# TTGO_shield_revF.net
KiCad netlist of a schematic drawn in EAGLE
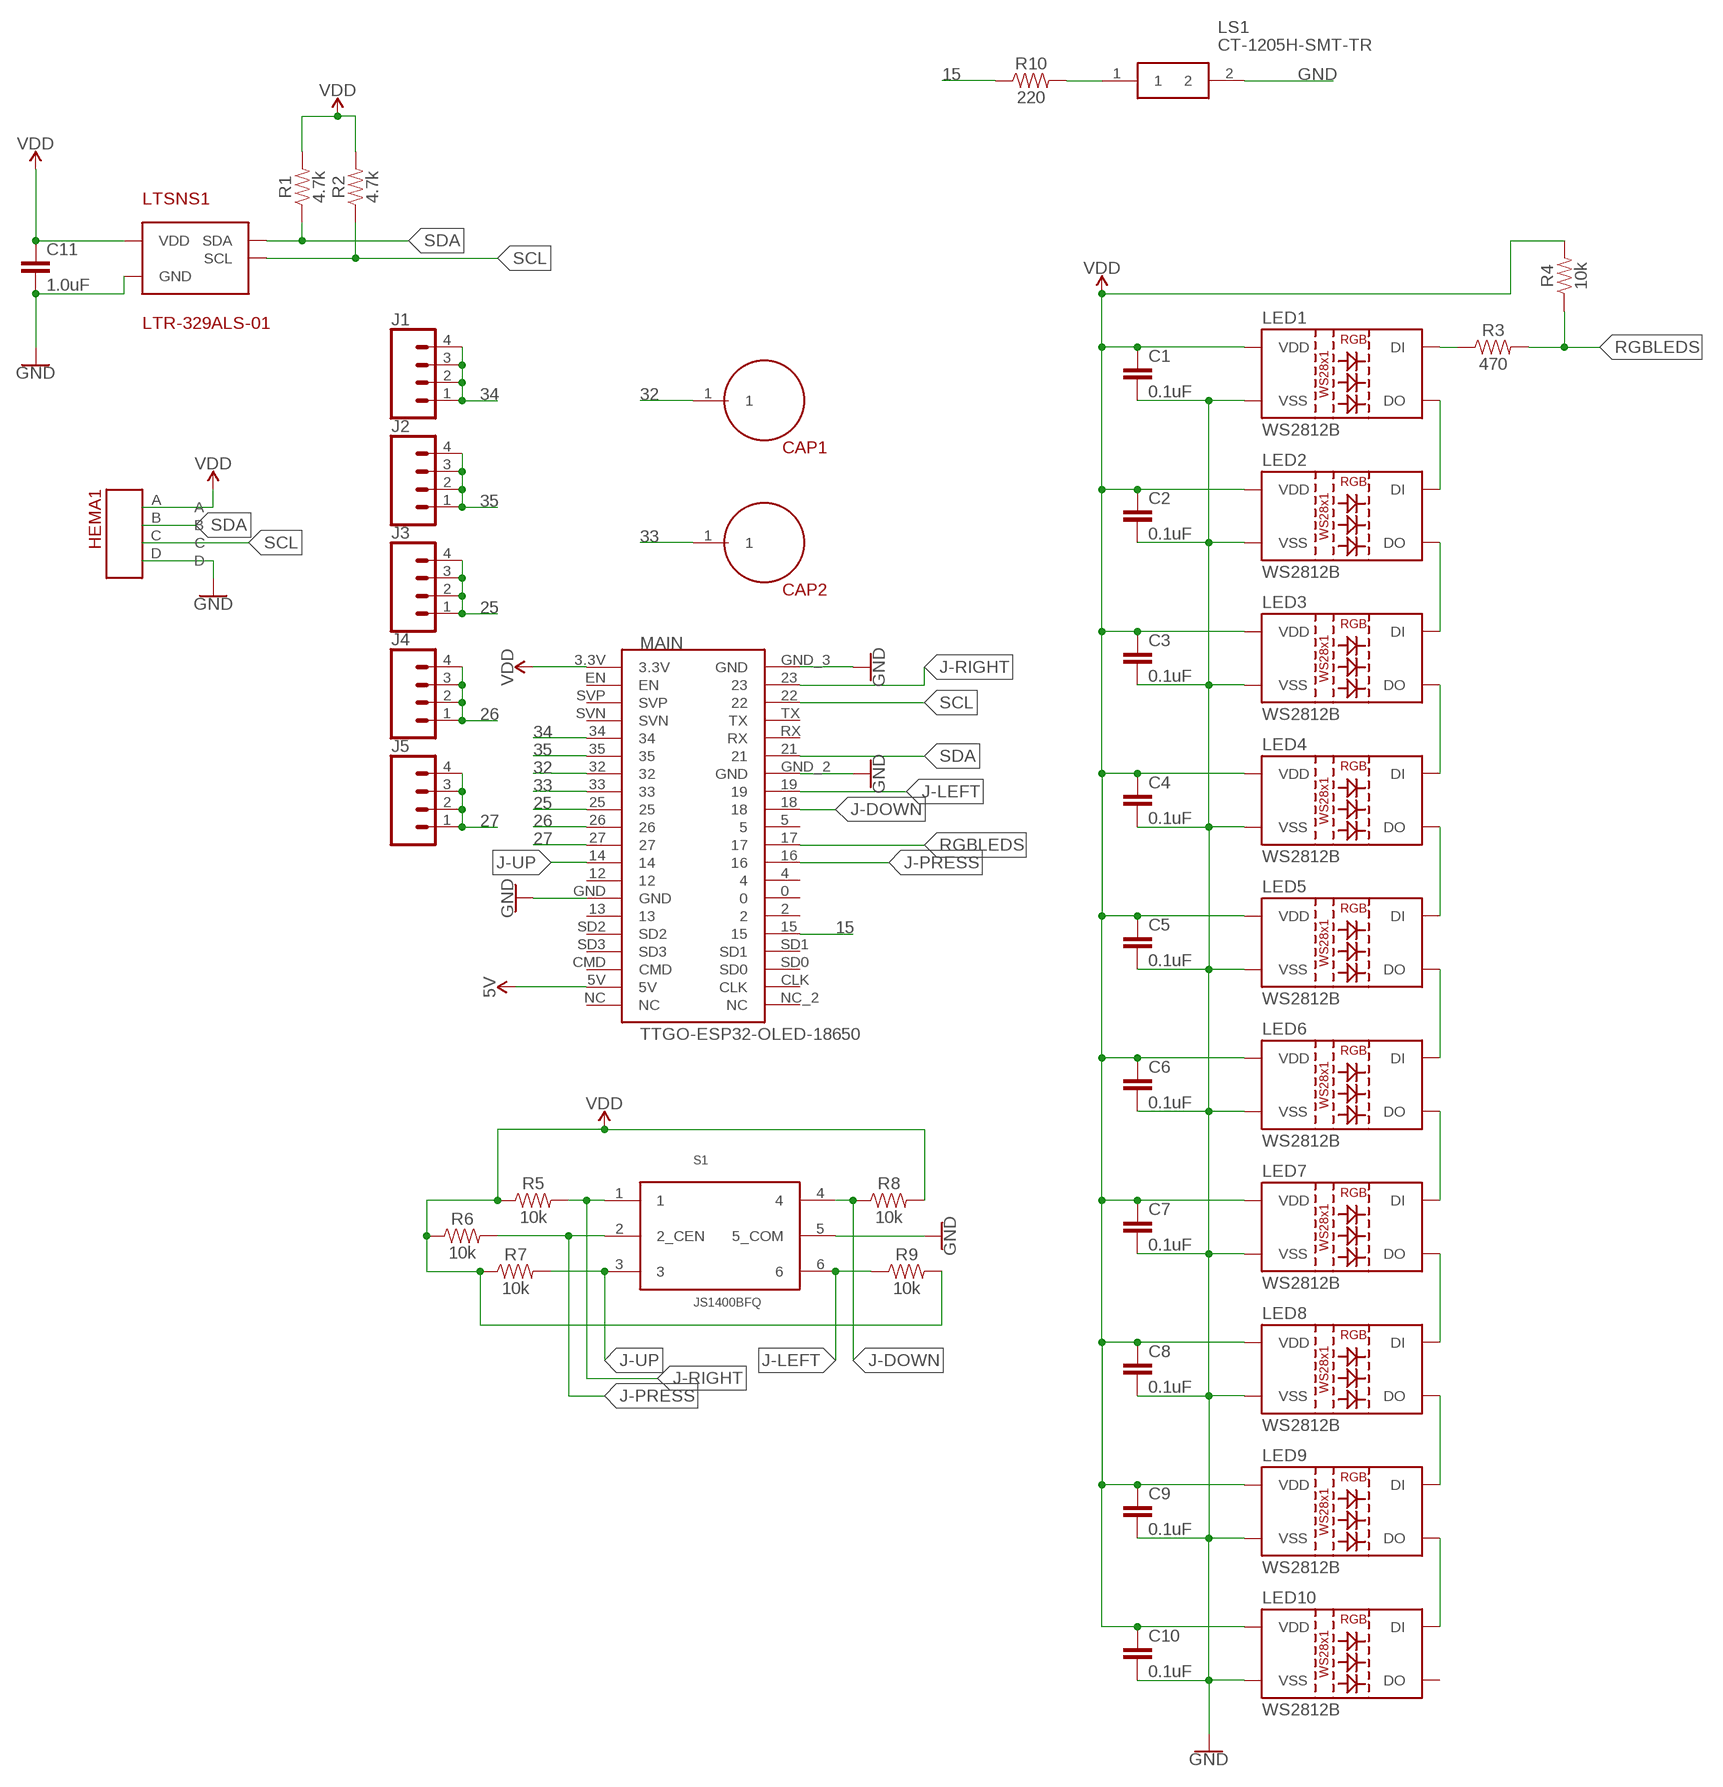
[diagram p0: schematic, sheet 1]

(export (version "E")
  (design (tool "Eeschema 10.0.6"))
  (components
    (comp (ref "C1")
      (value "0.1uF")
      (footprint "eagle-import:0603")
      (libsource (lib "eagle-import") (part "0.1UF-0603-25V-5%"))
    )
    (comp (ref "C2")
      (value "0.1uF")
      (footprint "eagle-import:0603")
      (libsource (lib "eagle-import") (part "0.1UF-0603-25V-5%"))
    )
    (comp (ref "C3")
      (value "0.1uF")
      (footprint "eagle-import:0603")
      (libsource (lib "eagle-import") (part "0.1UF-0603-25V-5%"))
    )
    (comp (ref "C4")
      (value "0.1uF")
      (footprint "eagle-import:0603")
      (libsource (lib "eagle-import") (part "0.1UF-0603-25V-5%"))
    )
    (comp (ref "C5")
      (value "0.1uF")
      (footprint "eagle-import:0603")
      (libsource (lib "eagle-import") (part "0.1UF-0603-25V-5%"))
    )
    (comp (ref "C6")
      (value "0.1uF")
      (footprint "eagle-import:0603")
      (libsource (lib "eagle-import") (part "0.1UF-0603-25V-5%"))
    )
    (comp (ref "C7")
      (value "0.1uF")
      (footprint "eagle-import:0603")
      (libsource (lib "eagle-import") (part "0.1UF-0603-25V-5%"))
    )
    (comp (ref "C8")
      (value "0.1uF")
      (footprint "eagle-import:0603")
      (libsource (lib "eagle-import") (part "0.1UF-0603-25V-5%"))
    )
    (comp (ref "C9")
      (value "0.1uF")
      (footprint "eagle-import:0603")
      (libsource (lib "eagle-import") (part "0.1UF-0603-25V-5%"))
    )
    (comp (ref "C10")
      (value "0.1uF")
      (footprint "eagle-import:0603")
      (libsource (lib "eagle-import") (part "0.1UF-0603-25V-5%"))
    )
    (comp (ref "C11")
      (value "1.0uF")
      (footprint "eagle-import:0805")
      (libsource (lib "eagle-import") (part "1.0UF-0805-25V-10%"))
    )
    (comp (ref "CAP1")
      (value "CAPSENSE_BUTTON")
      (footprint "eagle-import:CAPSENSE_BUTTON")
      (libsource (lib "eagle-import") (part "CAPSENSE_BUTTON"))
    )
    (comp (ref "CAP2")
      (value "CAPSENSE_BUTTON")
      (footprint "eagle-import:CAPSENSE_BUTTON")
      (libsource (lib "eagle-import") (part "CAPSENSE_BUTTON"))
    )
    (comp (ref "HEMA1")
      (value "10120045-400LF")
      (footprint "eagle-import:10120045-400LF")
      (libsource (lib "eagle-import") (part "10120045-400LF"))
    )
    (comp (ref "J1")
      (value "CONN_04LONGPADS")
      (footprint "eagle-import:1X04_LONGPADS")
      (libsource (lib "eagle-import") (part "CONN_04LONGPADS"))
    )
    (comp (ref "J2")
      (value "CONN_04LONGPADS")
      (footprint "eagle-import:1X04_LONGPADS")
      (libsource (lib "eagle-import") (part "CONN_04LONGPADS"))
    )
    (comp (ref "J3")
      (value "CONN_04LONGPADS")
      (footprint "eagle-import:1X04_LONGPADS")
      (libsource (lib "eagle-import") (part "CONN_04LONGPADS"))
    )
    (comp (ref "J4")
      (value "CONN_04LONGPADS")
      (footprint "eagle-import:1X04_LONGPADS")
      (libsource (lib "eagle-import") (part "CONN_04LONGPADS"))
    )
    (comp (ref "J5")
      (value "CONN_04LONGPADS")
      (footprint "eagle-import:1X04_LONGPADS")
      (libsource (lib "eagle-import") (part "CONN_04LONGPADS"))
    )
    (comp (ref "LED1")
      (value "WS2812B")
      (footprint "eagle-import:WS2812B")
      (libsource (lib "eagle-import") (part "WS2812B"))
    )
    (comp (ref "LED2")
      (value "WS2812B")
      (footprint "eagle-import:WS2812B")
      (libsource (lib "eagle-import") (part "WS2812B"))
    )
    (comp (ref "LED3")
      (value "WS2812B")
      (footprint "eagle-import:WS2812B")
      (libsource (lib "eagle-import") (part "WS2812B"))
    )
    (comp (ref "LED4")
      (value "WS2812B")
      (footprint "eagle-import:WS2812B")
      (libsource (lib "eagle-import") (part "WS2812B"))
    )
    (comp (ref "LED5")
      (value "WS2812B")
      (footprint "eagle-import:WS2812B")
      (libsource (lib "eagle-import") (part "WS2812B"))
    )
    (comp (ref "LED6")
      (value "WS2812B")
      (footprint "eagle-import:WS2812B")
      (libsource (lib "eagle-import") (part "WS2812B"))
    )
    (comp (ref "LED7")
      (value "WS2812B")
      (footprint "eagle-import:WS2812B")
      (libsource (lib "eagle-import") (part "WS2812B"))
    )
    (comp (ref "LED8")
      (value "WS2812B")
      (footprint "eagle-import:WS2812B")
      (libsource (lib "eagle-import") (part "WS2812B"))
    )
    (comp (ref "LED9")
      (value "WS2812B")
      (footprint "eagle-import:WS2812B")
      (libsource (lib "eagle-import") (part "WS2812B"))
    )
    (comp (ref "LED10")
      (value "WS2812B")
      (footprint "eagle-import:WS2812B")
      (libsource (lib "eagle-import") (part "WS2812B"))
    )
    (comp (ref "LS1")
      (value "CT-1205H-SMT-TR")
      (footprint "eagle-import:CT1205HSMTTR")
      (libsource (lib "eagle-import") (part "CT-1205H-SMT-TR"))
    )
    (comp (ref "LTSNS1")
      (value "LTR-329ALS-01")
      (footprint "eagle-import:CHIPLED-4")
      (libsource (lib "eagle-import") (part "LTR-329ALS-01"))
    )
    (comp (ref "MAIN")
      (value "TTGO-ESP32-OLED-18650")
      (footprint "eagle-import:TTGO-ESP32-OLED-18650")
      (libsource (lib "eagle-import") (part "TTGO-ESP32-OLED-18650"))
    )
    (comp (ref "R1")
      (value "4.7k")
      (footprint "eagle-import:0603")
      (libsource (lib "eagle-import") (part "4.7KOHM-0603-1/10W-1%"))
    )
    (comp (ref "R2")
      (value "4.7k")
      (footprint "eagle-import:0603")
      (libsource (lib "eagle-import") (part "4.7KOHM-0603-1/10W-1%"))
    )
    (comp (ref "R3")
      (value "470")
      (footprint "eagle-import:0603")
      (libsource (lib "eagle-import") (part "470OHM-0603-1/10W-1%"))
    )
    (comp (ref "R4")
      (value "10k")
      (footprint "eagle-import:0603")
      (libsource (lib "eagle-import") (part "10KOHM-0603-1/10W-1%"))
    )
    (comp (ref "R5")
      (value "10k")
      (footprint "eagle-import:0603")
      (libsource (lib "eagle-import") (part "10KOHM-0603-1/10W-1%"))
    )
    (comp (ref "R6")
      (value "10k")
      (footprint "eagle-import:0603")
      (libsource (lib "eagle-import") (part "10KOHM-0603-1/10W-1%"))
    )
    (comp (ref "R7")
      (value "10k")
      (footprint "eagle-import:0603")
      (libsource (lib "eagle-import") (part "10KOHM-0603-1/10W-1%"))
    )
    (comp (ref "R8")
      (value "10k")
      (footprint "eagle-import:0603")
      (libsource (lib "eagle-import") (part "10KOHM-0603-1/10W-1%"))
    )
    (comp (ref "R9")
      (value "10k")
      (footprint "eagle-import:0603")
      (libsource (lib "eagle-import") (part "10KOHM-0603-1/10W-1%"))
    )
    (comp (ref "R10")
      (value "220")
      (footprint "eagle-import:0603")
      (libsource (lib "eagle-import") (part "470OHM-0603-1/10W-1%"))
    )
    (comp (ref "S1")
      (value "JS1400BFQ")
      (footprint "eagle-import:JS1400BFQ")
      (libsource (lib "eagle-import") (part "JS1400BFQ"))
    )
  )
  (nets
    (net (code "1") (name "/15") (class "Default")
      (node (ref "MAIN") (pin "15") (pinfunction "15_15") (pintype "bidirectional"))
      (node (ref "R10") (pin "1") (pinfunction "1_1") (pintype "passive"))
    )
    (net (code "2") (name "/25") (class "Default")
      (node (ref "J3") (pin "1") (pinfunction "1_1") (pintype "passive"))
      (node (ref "J3") (pin "2") (pinfunction "2_2") (pintype "passive"))
      (node (ref "J3") (pin "3") (pinfunction "3_3") (pintype "passive"))
      (node (ref "J3") (pin "4") (pinfunction "4_4") (pintype "passive"))
      (node (ref "MAIN") (pin "25") (pinfunction "25_25") (pintype "bidirectional"))
    )
    (net (code "3") (name "/26") (class "Default")
      (node (ref "J4") (pin "1") (pinfunction "1_1") (pintype "passive"))
      (node (ref "J4") (pin "2") (pinfunction "2_2") (pintype "passive"))
      (node (ref "J4") (pin "3") (pinfunction "3_3") (pintype "passive"))
      (node (ref "J4") (pin "4") (pinfunction "4_4") (pintype "passive"))
      (node (ref "MAIN") (pin "26") (pinfunction "26_26") (pintype "bidirectional"))
    )
    (net (code "4") (name "/27") (class "Default")
      (node (ref "J5") (pin "1") (pinfunction "1_1") (pintype "passive"))
      (node (ref "J5") (pin "2") (pinfunction "2_2") (pintype "passive"))
      (node (ref "J5") (pin "3") (pinfunction "3_3") (pintype "passive"))
      (node (ref "J5") (pin "4") (pinfunction "4_4") (pintype "passive"))
      (node (ref "MAIN") (pin "27") (pinfunction "27_27") (pintype "bidirectional"))
    )
    (net (code "5") (name "/32") (class "Default")
      (node (ref "CAP1") (pin "1") (pinfunction "1_1") (pintype "bidirectional"))
      (node (ref "MAIN") (pin "32") (pinfunction "32_32") (pintype "bidirectional"))
    )
    (net (code "6") (name "/33") (class "Default")
      (node (ref "CAP2") (pin "1") (pinfunction "1_1") (pintype "bidirectional"))
      (node (ref "MAIN") (pin "33") (pinfunction "33_33") (pintype "bidirectional"))
    )
    (net (code "7") (name "/34") (class "Default")
      (node (ref "J1") (pin "1") (pinfunction "1_1") (pintype "passive"))
      (node (ref "J1") (pin "2") (pinfunction "2_2") (pintype "passive"))
      (node (ref "J1") (pin "3") (pinfunction "3_3") (pintype "passive"))
      (node (ref "J1") (pin "4") (pinfunction "4_4") (pintype "passive"))
      (node (ref "MAIN") (pin "34") (pinfunction "34_34") (pintype "bidirectional"))
    )
    (net (code "8") (name "/35") (class "Default")
      (node (ref "J2") (pin "1") (pinfunction "1_1") (pintype "passive"))
      (node (ref "J2") (pin "2") (pinfunction "2_2") (pintype "passive"))
      (node (ref "J2") (pin "3") (pinfunction "3_3") (pintype "passive"))
      (node (ref "J2") (pin "4") (pinfunction "4_4") (pintype "passive"))
      (node (ref "MAIN") (pin "35") (pinfunction "35_35") (pintype "bidirectional"))
    )
    (net (code "9") (name "5V") (class "Default")
      (node (ref "MAIN") (pin "5V") (pinfunction "5V_5V") (pintype "bidirectional"))
    )
    (net (code "10") (name "GND") (class "Default")
      (node (ref "C1") (pin "2") (pinfunction "2_2") (pintype "passive"))
      (node (ref "C10") (pin "2") (pinfunction "2_2") (pintype "passive"))
      (node (ref "C11") (pin "2") (pinfunction "2_2") (pintype "passive"))
      (node (ref "C2") (pin "2") (pinfunction "2_2") (pintype "passive"))
      (node (ref "C3") (pin "2") (pinfunction "2_2") (pintype "passive"))
      (node (ref "C4") (pin "2") (pinfunction "2_2") (pintype "passive"))
      (node (ref "C5") (pin "2") (pinfunction "2_2") (pintype "passive"))
      (node (ref "C6") (pin "2") (pinfunction "2_2") (pintype "passive"))
      (node (ref "C7") (pin "2") (pinfunction "2_2") (pintype "passive"))
      (node (ref "C8") (pin "2") (pinfunction "2_2") (pintype "passive"))
      (node (ref "C9") (pin "2") (pinfunction "2_2") (pintype "passive"))
      (node (ref "HEMA1") (pin "D") (pinfunction "D_D") (pintype "bidirectional"))
      (node (ref "LED1") (pin "3") (pinfunction "VSS_3") (pintype "bidirectional"))
      (node (ref "LED10") (pin "3") (pinfunction "VSS_3") (pintype "bidirectional"))
      (node (ref "LED2") (pin "3") (pinfunction "VSS_3") (pintype "bidirectional"))
      (node (ref "LED3") (pin "3") (pinfunction "VSS_3") (pintype "bidirectional"))
      (node (ref "LED4") (pin "3") (pinfunction "VSS_3") (pintype "bidirectional"))
      (node (ref "LED5") (pin "3") (pinfunction "VSS_3") (pintype "bidirectional"))
      (node (ref "LED6") (pin "3") (pinfunction "VSS_3") (pintype "bidirectional"))
      (node (ref "LED7") (pin "3") (pinfunction "VSS_3") (pintype "bidirectional"))
      (node (ref "LED8") (pin "3") (pinfunction "VSS_3") (pintype "bidirectional"))
      (node (ref "LED9") (pin "3") (pinfunction "VSS_3") (pintype "bidirectional"))
      (node (ref "LS1") (pin "2") (pinfunction "2_2") (pintype "bidirectional"))
      (node (ref "LTSNS1") (pin "2") (pinfunction "GND_2") (pintype "bidirectional"))
      (node (ref "MAIN") (pin "GND") (pinfunction "GND_GND") (pintype "bidirectional"))
      (node (ref "MAIN") (pin "GND_2") (pinfunction "GND_GND_2") (pintype "bidirectional"))
      (node (ref "MAIN") (pin "GND_3") (pinfunction "GND_GND_3") (pintype "bidirectional"))
      (node (ref "S1") (pin "5") (pinfunction "5_COM_5") (pintype "bidirectional"))
    )
    (net (code "11") (name "J-DOWN") (class "Default")
      (node (ref "MAIN") (pin "18") (pinfunction "18_18") (pintype "bidirectional"))
      (node (ref "R8") (pin "1") (pinfunction "1_1") (pintype "passive"))
      (node (ref "S1") (pin "4") (pinfunction "4_4") (pintype "bidirectional"))
    )
    (net (code "12") (name "J-LEFT") (class "Default")
      (node (ref "MAIN") (pin "19") (pinfunction "19_19") (pintype "bidirectional"))
      (node (ref "R9") (pin "1") (pinfunction "1_1") (pintype "passive"))
      (node (ref "S1") (pin "6") (pinfunction "6_6") (pintype "bidirectional"))
    )
    (net (code "13") (name "J-PRESS") (class "Default")
      (node (ref "MAIN") (pin "16") (pinfunction "16_16") (pintype "bidirectional"))
      (node (ref "R6") (pin "2") (pinfunction "2_2") (pintype "passive"))
      (node (ref "S1") (pin "2") (pinfunction "2_CEN_2") (pintype "bidirectional"))
    )
    (net (code "14") (name "J-RIGHT") (class "Default")
      (node (ref "MAIN") (pin "23") (pinfunction "23_23") (pintype "bidirectional"))
      (node (ref "R5") (pin "2") (pinfunction "2_2") (pintype "passive"))
      (node (ref "S1") (pin "1") (pinfunction "1_1") (pintype "bidirectional"))
    )
    (net (code "15") (name "J-UP") (class "Default")
      (node (ref "MAIN") (pin "14") (pinfunction "14_14") (pintype "bidirectional"))
      (node (ref "R7") (pin "2") (pinfunction "2_2") (pintype "passive"))
      (node (ref "S1") (pin "3") (pinfunction "3_3") (pintype "bidirectional"))
    )
    (net (code "16") (name "Net-(LED1-DI)") (class "Default")
      (node (ref "LED1") (pin "4") (pinfunction "DI_4") (pintype "bidirectional"))
      (node (ref "R3") (pin "1") (pinfunction "1_1") (pintype "passive"))
    )
    (net (code "17") (name "Net-(LED1-DO)") (class "Default")
      (node (ref "LED1") (pin "2") (pinfunction "DO_2") (pintype "bidirectional"))
      (node (ref "LED2") (pin "4") (pinfunction "DI_4") (pintype "bidirectional"))
    )
    (net (code "18") (name "Net-(LED2-DO)") (class "Default")
      (node (ref "LED2") (pin "2") (pinfunction "DO_2") (pintype "bidirectional"))
      (node (ref "LED3") (pin "4") (pinfunction "DI_4") (pintype "bidirectional"))
    )
    (net (code "19") (name "Net-(LED3-DO)") (class "Default")
      (node (ref "LED3") (pin "2") (pinfunction "DO_2") (pintype "bidirectional"))
      (node (ref "LED4") (pin "4") (pinfunction "DI_4") (pintype "bidirectional"))
    )
    (net (code "20") (name "Net-(LED4-DO)") (class "Default")
      (node (ref "LED4") (pin "2") (pinfunction "DO_2") (pintype "bidirectional"))
      (node (ref "LED5") (pin "4") (pinfunction "DI_4") (pintype "bidirectional"))
    )
    (net (code "21") (name "Net-(LED5-DO)") (class "Default")
      (node (ref "LED5") (pin "2") (pinfunction "DO_2") (pintype "bidirectional"))
      (node (ref "LED6") (pin "4") (pinfunction "DI_4") (pintype "bidirectional"))
    )
    (net (code "22") (name "Net-(LED6-DO)") (class "Default")
      (node (ref "LED6") (pin "2") (pinfunction "DO_2") (pintype "bidirectional"))
      (node (ref "LED7") (pin "4") (pinfunction "DI_4") (pintype "bidirectional"))
    )
    (net (code "23") (name "Net-(LED7-DO)") (class "Default")
      (node (ref "LED7") (pin "2") (pinfunction "DO_2") (pintype "bidirectional"))
      (node (ref "LED8") (pin "4") (pinfunction "DI_4") (pintype "bidirectional"))
    )
    (net (code "24") (name "Net-(LED8-DO)") (class "Default")
      (node (ref "LED8") (pin "2") (pinfunction "DO_2") (pintype "bidirectional"))
      (node (ref "LED9") (pin "4") (pinfunction "DI_4") (pintype "bidirectional"))
    )
    (net (code "25") (name "Net-(LED10-DI)") (class "Default")
      (node (ref "LED10") (pin "4") (pinfunction "DI_4") (pintype "bidirectional"))
      (node (ref "LED9") (pin "2") (pinfunction "DO_2") (pintype "bidirectional"))
    )
    (net (code "26") (name "Net-(LS1-Pad1)") (class "Default")
      (node (ref "LS1") (pin "1") (pinfunction "1_1") (pintype "bidirectional"))
      (node (ref "R10") (pin "2") (pinfunction "2_2") (pintype "passive"))
    )
    (net (code "27") (name "RGBLEDS") (class "Default")
      (node (ref "MAIN") (pin "17") (pinfunction "17_17") (pintype "bidirectional"))
      (node (ref "R3") (pin "2") (pinfunction "2_2") (pintype "passive"))
      (node (ref "R4") (pin "1") (pinfunction "1_1") (pintype "passive"))
    )
    (net (code "28") (name "SCL") (class "Default")
      (node (ref "HEMA1") (pin "C") (pinfunction "C_C") (pintype "bidirectional"))
      (node (ref "LTSNS1") (pin "4") (pinfunction "SCL_4") (pintype "bidirectional"))
      (node (ref "MAIN") (pin "22") (pinfunction "22_22") (pintype "bidirectional"))
      (node (ref "R2") (pin "1") (pinfunction "1_1") (pintype "passive"))
    )
    (net (code "29") (name "SDA") (class "Default")
      (node (ref "HEMA1") (pin "B") (pinfunction "B_B") (pintype "bidirectional"))
      (node (ref "LTSNS1") (pin "3") (pinfunction "SDA_3") (pintype "bidirectional"))
      (node (ref "MAIN") (pin "21") (pinfunction "21_21") (pintype "bidirectional"))
      (node (ref "R1") (pin "1") (pinfunction "1_1") (pintype "passive"))
    )
    (net (code "30") (name "VDD") (class "Default")
      (node (ref "C1") (pin "1") (pinfunction "1_1") (pintype "passive"))
      (node (ref "C10") (pin "1") (pinfunction "1_1") (pintype "passive"))
      (node (ref "C11") (pin "1") (pinfunction "1_1") (pintype "passive"))
      (node (ref "C2") (pin "1") (pinfunction "1_1") (pintype "passive"))
      (node (ref "C3") (pin "1") (pinfunction "1_1") (pintype "passive"))
      (node (ref "C4") (pin "1") (pinfunction "1_1") (pintype "passive"))
      (node (ref "C5") (pin "1") (pinfunction "1_1") (pintype "passive"))
      (node (ref "C6") (pin "1") (pinfunction "1_1") (pintype "passive"))
      (node (ref "C7") (pin "1") (pinfunction "1_1") (pintype "passive"))
      (node (ref "C8") (pin "1") (pinfunction "1_1") (pintype "passive"))
      (node (ref "C9") (pin "1") (pinfunction "1_1") (pintype "passive"))
      (node (ref "HEMA1") (pin "A") (pinfunction "A_A") (pintype "bidirectional"))
      (node (ref "LED1") (pin "1") (pinfunction "VDD_1") (pintype "bidirectional"))
      (node (ref "LED10") (pin "1") (pinfunction "VDD_1") (pintype "bidirectional"))
      (node (ref "LED2") (pin "1") (pinfunction "VDD_1") (pintype "bidirectional"))
      (node (ref "LED3") (pin "1") (pinfunction "VDD_1") (pintype "bidirectional"))
      (node (ref "LED4") (pin "1") (pinfunction "VDD_1") (pintype "bidirectional"))
      (node (ref "LED5") (pin "1") (pinfunction "VDD_1") (pintype "bidirectional"))
      (node (ref "LED6") (pin "1") (pinfunction "VDD_1") (pintype "bidirectional"))
      (node (ref "LED7") (pin "1") (pinfunction "VDD_1") (pintype "bidirectional"))
      (node (ref "LED8") (pin "1") (pinfunction "VDD_1") (pintype "bidirectional"))
      (node (ref "LED9") (pin "1") (pinfunction "VDD_1") (pintype "bidirectional"))
      (node (ref "LTSNS1") (pin "1") (pinfunction "VDD_1") (pintype "bidirectional"))
      (node (ref "MAIN") (pin "3.3V") (pinfunction "3.3V_3.3V") (pintype "bidirectional"))
      (node (ref "R1") (pin "2") (pinfunction "2_2") (pintype "passive"))
      (node (ref "R2") (pin "2") (pinfunction "2_2") (pintype "passive"))
      (node (ref "R4") (pin "2") (pinfunction "2_2") (pintype "passive"))
      (node (ref "R5") (pin "1") (pinfunction "1_1") (pintype "passive"))
      (node (ref "R6") (pin "1") (pinfunction "1_1") (pintype "passive"))
      (node (ref "R7") (pin "1") (pinfunction "1_1") (pintype "passive"))
      (node (ref "R8") (pin "2") (pinfunction "2_2") (pintype "passive"))
      (node (ref "R9") (pin "2") (pinfunction "2_2") (pintype "passive"))
    )
    (net (code "31") (name "unconnected-(LED10-DO-Pad2)") (class "Default")
      (node (ref "LED10") (pin "2") (pinfunction "DO_2") (pintype "bidirectional"))
    )
    (net (code "32") (name "unconnected-(MAIN-NC-PadNC_2)") (class "Default")
      (node (ref "MAIN") (pin "NC_2") (pinfunction "NC_NC_2") (pintype "bidirectional"))
    )
    (net (code "33") (name "unconnected-(MAIN-Pad0)") (class "Default")
      (node (ref "MAIN") (pin "0") (pinfunction "0_0") (pintype "bidirectional"))
    )
    (net (code "34") (name "unconnected-(MAIN-Pad2)") (class "Default")
      (node (ref "MAIN") (pin "2") (pinfunction "2_2") (pintype "bidirectional"))
    )
    (net (code "35") (name "unconnected-(MAIN-Pad4)") (class "Default")
      (node (ref "MAIN") (pin "4") (pinfunction "4_4") (pintype "bidirectional"))
    )
    (net (code "36") (name "unconnected-(MAIN-Pad5)") (class "Default")
      (node (ref "MAIN") (pin "5") (pinfunction "5_5") (pintype "bidirectional"))
    )
    (net (code "37") (name "unconnected-(MAIN-Pad12)") (class "Default")
      (node (ref "MAIN") (pin "12") (pinfunction "12_12") (pintype "bidirectional"))
    )
    (net (code "38") (name "unconnected-(MAIN-Pad13)") (class "Default")
      (node (ref "MAIN") (pin "13") (pinfunction "13_13") (pintype "bidirectional"))
    )
    (net (code "39") (name "unconnected-(MAIN-PadCLK)") (class "Default")
      (node (ref "MAIN") (pin "CLK") (pinfunction "CLK_CLK") (pintype "bidirectional"))
    )
    (net (code "40") (name "unconnected-(MAIN-PadCMD)") (class "Default")
      (node (ref "MAIN") (pin "CMD") (pinfunction "CMD_CMD") (pintype "bidirectional"))
    )
    (net (code "41") (name "unconnected-(MAIN-PadEN)") (class "Default")
      (node (ref "MAIN") (pin "EN") (pinfunction "EN_EN") (pintype "bidirectional"))
    )
    (net (code "42") (name "unconnected-(MAIN-PadNC)") (class "Default")
      (node (ref "MAIN") (pin "NC") (pinfunction "NC_NC") (pintype "bidirectional"))
    )
    (net (code "43") (name "unconnected-(MAIN-PadRX)") (class "Default")
      (node (ref "MAIN") (pin "RX") (pinfunction "RX_RX") (pintype "bidirectional"))
    )
    (net (code "44") (name "unconnected-(MAIN-PadSD0)") (class "Default")
      (node (ref "MAIN") (pin "SD0") (pinfunction "SD0_SD0") (pintype "bidirectional"))
    )
    (net (code "45") (name "unconnected-(MAIN-PadSD1)") (class "Default")
      (node (ref "MAIN") (pin "SD1") (pinfunction "SD1_SD1") (pintype "bidirectional"))
    )
    (net (code "46") (name "unconnected-(MAIN-PadSD2)") (class "Default")
      (node (ref "MAIN") (pin "SD2") (pinfunction "SD2_SD2") (pintype "bidirectional"))
    )
    (net (code "47") (name "unconnected-(MAIN-PadSD3)") (class "Default")
      (node (ref "MAIN") (pin "SD3") (pinfunction "SD3_SD3") (pintype "bidirectional"))
    )
    (net (code "48") (name "unconnected-(MAIN-PadSVN)") (class "Default")
      (node (ref "MAIN") (pin "SVN") (pinfunction "SVN_SVN") (pintype "bidirectional"))
    )
    (net (code "49") (name "unconnected-(MAIN-PadSVP)") (class "Default")
      (node (ref "MAIN") (pin "SVP") (pinfunction "SVP_SVP") (pintype "bidirectional"))
    )
    (net (code "50") (name "unconnected-(MAIN-PadTX)") (class "Default")
      (node (ref "MAIN") (pin "TX") (pinfunction "TX_TX") (pintype "bidirectional"))
    )
  )
)
